# LED_Driver.net
KiCad netlist of a schematic drawn in Altium Designer
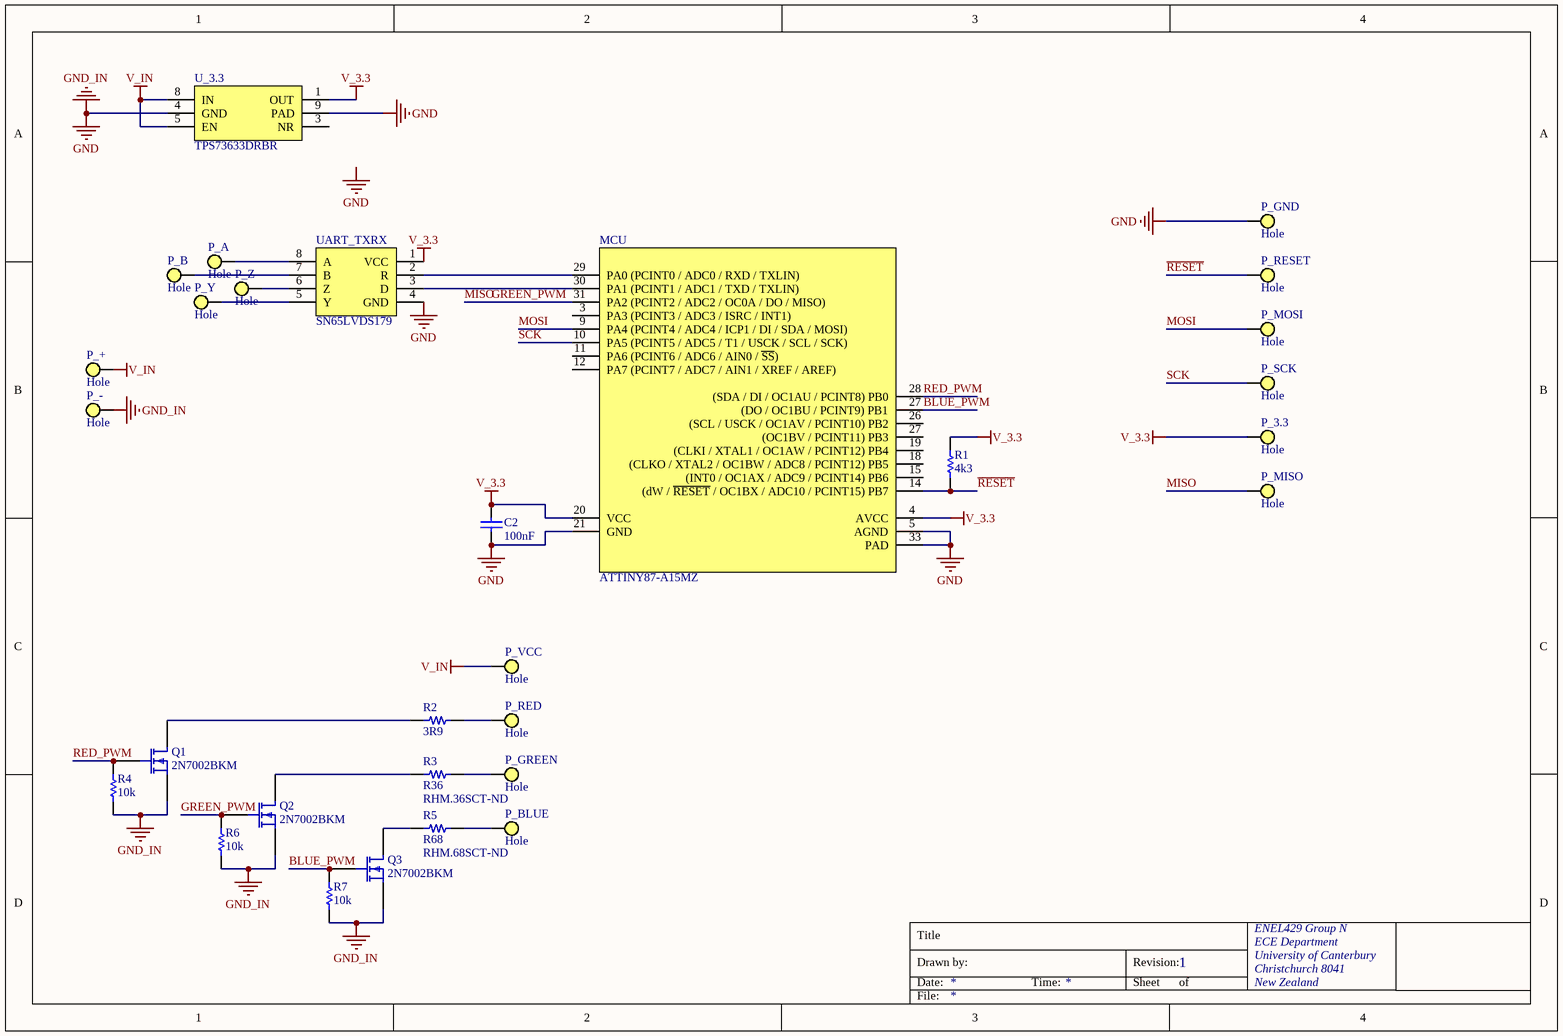
[diagram p0: LED_Driver.SchDoc]

(export (version "E")
  (design (tool "Eeschema 10.0.6"))
  (components
    (comp (ref "C2")
      (value "100nF")
      (footprint "0603")
      (description "CAP CER .10UF 50V X5R 0603")
      (fields (field (name "MANUFACTURER") "Taiyo Yuden") (field (name "PART NUMBER") "CP_100nF 0603"))
      (libsource (lib "ENEL429_4") (part "CP_100nF 0603"))
    )
    (comp (ref "MCU")
      (value "ATTINY87-A15MZ")
      (footprint "QFN50P500X500X100-32N")
      (description "MCU AVR 8K FLASH 15MHZ 32QFN")
      (fields (field (name "MANUFACTURER") "Atmel"))
      (libsource (lib "My Schematic Library") (part "ATTINY87-A15MZ"))
    )
    (comp (ref "P_+")
      (value "Hole")
      (footprint "Hole")
      (description "A hole to solder a wire to.")
      (libsource (lib "My Schematic Library") (part "Solder_Hole"))
    )
    (comp (ref "P_-")
      (value "Hole")
      (footprint "Hole")
      (description "A hole to solder a wire to.")
      (libsource (lib "My Schematic Library") (part "Solder_Hole"))
    )
    (comp (ref "P_3.3")
      (value "Hole")
      (footprint "Hole")
      (description "A hole to solder a wire to.")
      (libsource (lib "My Schematic Library") (part "Solder_Hole"))
    )
    (comp (ref "P_A")
      (value "Hole")
      (footprint "Hole")
      (description "A hole to solder a wire to.")
      (libsource (lib "My Schematic Library") (part "Solder_Hole"))
    )
    (comp (ref "P_B")
      (value "Hole")
      (footprint "Hole")
      (description "A hole to solder a wire to.")
      (libsource (lib "My Schematic Library") (part "Solder_Hole"))
    )
    (comp (ref "P_BLUE")
      (value "Hole")
      (footprint "Hole")
      (description "A hole to solder a wire to.")
      (libsource (lib "My Schematic Library") (part "Solder_Hole"))
    )
    (comp (ref "P_GND")
      (value "Hole")
      (footprint "Hole")
      (description "A hole to solder a wire to.")
      (libsource (lib "My Schematic Library") (part "Solder_Hole"))
    )
    (comp (ref "P_GREEN")
      (value "Hole")
      (footprint "Hole")
      (description "A hole to solder a wire to.")
      (libsource (lib "My Schematic Library") (part "Solder_Hole"))
    )
    (comp (ref "P_MISO")
      (value "Hole")
      (footprint "Hole")
      (description "A hole to solder a wire to.")
      (libsource (lib "My Schematic Library") (part "Solder_Hole"))
    )
    (comp (ref "P_MOSI")
      (value "Hole")
      (footprint "Hole")
      (description "A hole to solder a wire to.")
      (libsource (lib "My Schematic Library") (part "Solder_Hole"))
    )
    (comp (ref "P_RED")
      (value "Hole")
      (footprint "Hole")
      (description "A hole to solder a wire to.")
      (libsource (lib "My Schematic Library") (part "Solder_Hole"))
    )
    (comp (ref "P_RESET")
      (value "Hole")
      (footprint "Hole")
      (description "A hole to solder a wire to.")
      (libsource (lib "My Schematic Library") (part "Solder_Hole"))
    )
    (comp (ref "P_SCK")
      (value "Hole")
      (footprint "Hole")
      (description "A hole to solder a wire to.")
      (libsource (lib "My Schematic Library") (part "Solder_Hole"))
    )
    (comp (ref "P_VCC")
      (value "Hole")
      (footprint "Hole")
      (description "A hole to solder a wire to.")
      (libsource (lib "My Schematic Library") (part "Solder_Hole"))
    )
    (comp (ref "P_Y")
      (value "Hole")
      (footprint "Hole")
      (description "A hole to solder a wire to.")
      (libsource (lib "My Schematic Library") (part "Solder_Hole"))
    )
    (comp (ref "P_Z")
      (value "Hole")
      (footprint "Hole")
      (description "A hole to solder a wire to.")
      (libsource (lib "My Schematic Library") (part "Solder_Hole"))
    )
    (comp (ref "Q1")
      (value "2N7002BKM")
      (footprint "SOT883 / SC-101")
      (description "MOSFET N-CH 60V 450MA SOT883")
      (fields
        (field (name "MANUFACTURER") "NXP Semiconductors")
        (field (name "MANUFACTURER PART NUMBER") "2N7002BKM,315")
      )
      (libsource (lib "My Schematic Library") (part "2N7002BKM,315"))
    )
    (comp (ref "Q2")
      (value "2N7002BKM")
      (footprint "SOT883 / SC-101")
      (description "MOSFET N-CH 60V 450MA SOT883")
      (fields
        (field (name "MANUFACTURER") "NXP Semiconductors")
        (field (name "MANUFACTURER PART NUMBER") "2N7002BKM,315")
      )
      (libsource (lib "My Schematic Library") (part "2N7002BKM,315"))
    )
    (comp (ref "Q3")
      (value "2N7002BKM")
      (footprint "SOT883 / SC-101")
      (description "MOSFET N-CH 60V 450MA SOT883")
      (fields
        (field (name "MANUFACTURER") "NXP Semiconductors")
        (field (name "MANUFACTURER PART NUMBER") "2N7002BKM,315")
      )
      (libsource (lib "My Schematic Library") (part "2N7002BKM,315"))
    )
    (comp (ref "R1")
      (value "4k3")
      (footprint "0603")
      (description "RES 4.3K OHM 1/10W 5% 0603 SMD")
      (fields (field (name "MANUFACTURER") "Yageo") (field (name "PART NUMBER") "RS_4k3 0603"))
      (libsource (lib "ENEL429_4") (part "RS_4k3 0603"))
    )
    (comp (ref "R2")
      (value "3R9")
      (footprint "1210")
      (description "RES 3.9 OHM 1/2W 5% 1210 SMD")
      (fields
        (field (name "MANUFACTURER") "Vishay/Dale")
        (field (name "MANUFACTURER PART NUMBER") "CRCW12103R90JNEA")
      )
      (libsource (lib "My Schematic Library") (part "CRCW12103R90JNEA"))
    )
    (comp (ref "R3")
      (value "R36")
      (footprint "1210")
      (description "RES .36 OHM 1/2W 1% 1210 SMD")
      (fields
        (field (name "MANUFACTURER") "Rohm Semiconductor")
        (field (name "MANUFACTURER PART NUMBER") "MCR25JZHFLR360")
        (field (name "SUPPLIER PART NUMBER 1") "RHM.36SCT-ND")
      )
      (libsource (lib "My Schematic Library") (part "MCR25JZHFLR360"))
    )
    (comp (ref "R4")
      (value "10k")
      (footprint "0603")
      (description "RES 10.0K OHM 1/10W 1% 0603 SMD")
      (fields (field (name "MANUFACTURER") "Yageo") (field (name "PART NUMBER") "RS_10k 0603"))
      (libsource (lib "ENEL429_4") (part "RS_10k 0603"))
    )
    (comp (ref "R5")
      (value "R68")
      (footprint "1210")
      (description "RES .68 OHM 1/2W 1% 1210 SMD")
      (fields
        (field (name "MANUFACTURER") "Rohm Semiconductor")
        (field (name "MANUFACTURER PART NUMBER") "MCR25JZHFLR680")
        (field (name "SUPPLIER PART NUMBER 1") "RHM.68SCT-ND")
      )
      (libsource (lib "My Schematic Library") (part "MCR25JZHFLR680"))
    )
    (comp (ref "R6")
      (value "10k")
      (footprint "0603")
      (description "RES 10.0K OHM 1/10W 1% 0603 SMD")
      (fields (field (name "MANUFACTURER") "Yageo") (field (name "PART NUMBER") "RS_10k 0603"))
      (libsource (lib "ENEL429_4") (part "RS_10k 0603"))
    )
    (comp (ref "R7")
      (value "10k")
      (footprint "0603")
      (description "RES 10.0K OHM 1/10W 1% 0603 SMD")
      (fields (field (name "MANUFACTURER") "Yageo") (field (name "PART NUMBER") "RS_10k 0603"))
      (libsource (lib "ENEL429_4") (part "RS_10k 0603"))
    )
    (comp (ref "UART_TXRX")
      (value "SN65LVDS179")
      (footprint "TI - DGK / TSOP65P490X110-8L")
      (description "High-Speed Differential Line Driver and Receiver")
      (fields
        (field (name "MANUFACTURER") "Texas Instruments")
        (field (name "MANUFACTURER PART NUMBER") "SN65LVDS179DGK")
      )
      (libsource (lib "My Schematic Library") (part "SN65LVDS179DGK"))
    )
    (comp (ref "U_3.3")
      (value "TPS73633DRBR")
      (footprint "TI - DRB / QFN65P300X300X100-8L")
      (description "IC LDO REG 400MA NO CAP 8-SON")
      (fields (field (name "MANUFACTURER") "Texas Instruments"))
      (libsource (lib "My Schematic Library") (part "TPS73633DRBR"))
    )
  )
  (nets
    (net (code "1") (name "/BLUE_PWM") (class "Default")
      (node (ref "MCU") (pin "27") (pinfunction "(DO_/_OC1BU_/_PCINT9)_PB1_27") (pintype "passive"))
      (node (ref "Q3") (pin "1") (pinfunction "G_1") (pintype "passive"))
      (node (ref "R7") (pin "2") (pinfunction "2_2") (pintype "passive"))
    )
    (net (code "2") (name "/GREEN_PWM") (class "Default")
      (node (ref "MCU") (pin "31") (pinfunction "PA2_(PCINT2_/_ADC2_/_OC0A_/_DO_/_MISO)_31") (pintype "passive"))
      (node (ref "P_MISO") (pin "1") (pintype "passive"))
      (node (ref "Q2") (pin "1") (pinfunction "G_1") (pintype "passive"))
      (node (ref "R6") (pin "2") (pinfunction "2_2") (pintype "passive"))
    )
    (net (code "3") (name "/MOSI") (class "Default")
      (node (ref "MCU") (pin "9") (pinfunction "PA4_(PCINT4_/_ADC4_/_ICP1_/_DI_/_SDA_/_MOSI)_9") (pintype "passive"))
      (node (ref "P_MOSI") (pin "1") (pintype "passive"))
    )
    (net (code "4") (name "/RED_PWM") (class "Default")
      (node (ref "MCU") (pin "28") (pinfunction "(SDA_/_DI_/_OC1AU_/_PCINT8)_PB0_28") (pintype "passive"))
      (node (ref "Q1") (pin "1") (pinfunction "G_1") (pintype "passive"))
      (node (ref "R4") (pin "2") (pinfunction "2_2") (pintype "passive"))
    )
    (net (code "5") (name "/SCK") (class "Default")
      (node (ref "MCU") (pin "10") (pinfunction "PA5_(PCINT5_/_ADC5_/_T1_/_USCK_/_SCL_/_SCK)_10") (pintype "passive"))
      (node (ref "P_SCK") (pin "1") (pintype "passive"))
    )
    (net (code "6") (name "/~{RESET}") (class "Default")
      (node (ref "MCU") (pin "14") (pinfunction "(dW_/_~{RESET}_/_OC1BX_/_ADC10_/_PCINT15)_PB7_14") (pintype "passive"))
      (node (ref "P_RESET") (pin "1") (pintype "passive"))
      (node (ref "R1") (pin "1") (pinfunction "1_1") (pintype "passive"))
    )
    (net (code "7") (name "GND") (class "Default")
      (node (ref "C2") (pin "1") (pinfunction "1_1") (pintype "passive"))
      (node (ref "MCU") (pin "21") (pinfunction "GND_21") (pintype "passive"))
      (node (ref "MCU") (pin "33") (pinfunction "PAD_33") (pintype "passive"))
      (node (ref "MCU") (pin "5") (pinfunction "AGND_5") (pintype "passive"))
      (node (ref "P_-") (pin "1") (pintype "passive"))
      (node (ref "P_GND") (pin "1") (pintype "passive"))
      (node (ref "Q1") (pin "2") (pinfunction "S_2") (pintype "passive"))
      (node (ref "Q2") (pin "2") (pinfunction "S_2") (pintype "passive"))
      (node (ref "Q3") (pin "2") (pinfunction "S_2") (pintype "passive"))
      (node (ref "R4") (pin "1") (pinfunction "1_1") (pintype "passive"))
      (node (ref "R6") (pin "1") (pinfunction "1_1") (pintype "passive"))
      (node (ref "R7") (pin "1") (pinfunction "1_1") (pintype "passive"))
      (node (ref "UART_TXRX") (pin "4") (pinfunction "GND_4") (pintype "passive"))
      (node (ref "U_3.3") (pin "4") (pinfunction "GND_4") (pintype "passive"))
      (node (ref "U_3.3") (pin "9") (pinfunction "PAD_9") (pintype "passive"))
    )
    (net (code "8") (name "Net-(MCU-PA0_(PCINT0_{slash}_ADC0_{slash}_RXD_{slash}_TXLIN))") (class "Default")
      (node (ref "MCU") (pin "29") (pinfunction "PA0_(PCINT0_/_ADC0_/_RXD_/_TXLIN)_29") (pintype "passive"))
      (node (ref "UART_TXRX") (pin "2") (pinfunction "R_2") (pintype "passive"))
    )
    (net (code "9") (name "Net-(MCU-PA1_(PCINT1_{slash}_ADC1_{slash}_TXD_{slash}_TXLIN))") (class "Default")
      (node (ref "MCU") (pin "30") (pinfunction "PA1_(PCINT1_/_ADC1_/_TXD_/_TXLIN)_30") (pintype "passive"))
      (node (ref "UART_TXRX") (pin "3") (pinfunction "D_3") (pintype "passive"))
    )
    (net (code "10") (name "Net-(P_BLUE-Pad1)") (class "Default")
      (node (ref "P_BLUE") (pin "1") (pintype "passive"))
      (node (ref "R5") (pin "2") (pintype "passive"))
    )
    (net (code "11") (name "Net-(P_GREEN-Pad1)") (class "Default")
      (node (ref "P_GREEN") (pin "1") (pintype "passive"))
      (node (ref "R3") (pin "2") (pintype "passive"))
    )
    (net (code "12") (name "Net-(P_RED-Pad1)") (class "Default")
      (node (ref "P_RED") (pin "1") (pintype "passive"))
      (node (ref "R2") (pin "2") (pintype "passive"))
    )
    (net (code "13") (name "Net-(Q1-D)") (class "Default")
      (node (ref "Q1") (pin "3") (pinfunction "D_3") (pintype "passive"))
      (node (ref "R2") (pin "1") (pintype "passive"))
    )
    (net (code "14") (name "Net-(Q2-D)") (class "Default")
      (node (ref "Q2") (pin "3") (pinfunction "D_3") (pintype "passive"))
      (node (ref "R3") (pin "1") (pintype "passive"))
    )
    (net (code "15") (name "Net-(Q3-D)") (class "Default")
      (node (ref "Q3") (pin "3") (pinfunction "D_3") (pintype "passive"))
      (node (ref "R5") (pin "1") (pintype "passive"))
    )
    (net (code "16") (name "Net-(UART_TXRX-A)") (class "Default")
      (node (ref "P_A") (pin "1") (pintype "passive"))
      (node (ref "UART_TXRX") (pin "8") (pinfunction "A_8") (pintype "passive"))
    )
    (net (code "17") (name "Net-(UART_TXRX-B)") (class "Default")
      (node (ref "P_B") (pin "1") (pintype "passive"))
      (node (ref "UART_TXRX") (pin "7") (pinfunction "B_7") (pintype "passive"))
    )
    (net (code "18") (name "Net-(UART_TXRX-Y)") (class "Default")
      (node (ref "P_Y") (pin "1") (pintype "passive"))
      (node (ref "UART_TXRX") (pin "5") (pinfunction "Y_5") (pintype "passive"))
    )
    (net (code "19") (name "Net-(UART_TXRX-Z)") (class "Default")
      (node (ref "P_Z") (pin "1") (pintype "passive"))
      (node (ref "UART_TXRX") (pin "6") (pinfunction "Z_6") (pintype "passive"))
    )
    (net (code "20") (name "V_3.3") (class "Default")
      (node (ref "C2") (pin "2") (pinfunction "2_2") (pintype "passive"))
      (node (ref "MCU") (pin "20") (pinfunction "VCC_20") (pintype "passive"))
      (node (ref "MCU") (pin "4") (pinfunction "AVCC_4") (pintype "passive"))
      (node (ref "P_3.3") (pin "1") (pintype "passive"))
      (node (ref "R1") (pin "2") (pinfunction "2_2") (pintype "passive"))
      (node (ref "UART_TXRX") (pin "1") (pinfunction "VCC_1") (pintype "passive"))
      (node (ref "U_3.3") (pin "1") (pinfunction "OUT_1") (pintype "passive"))
    )
    (net (code "21") (name "V_IN") (class "Default")
      (node (ref "P_+") (pin "1") (pintype "passive"))
      (node (ref "P_VCC") (pin "1") (pintype "passive"))
      (node (ref "U_3.3") (pin "5") (pinfunction "EN_5") (pintype "passive"))
      (node (ref "U_3.3") (pin "8") (pinfunction "IN_8") (pintype "passive"))
    )
    (net (code "22") (name "unconnected-(MCU-(CLKI_{slash}_XTAL1_{slash}_OC1AW_{slash}_PCINT12)_PB4-Pad19)") (class "Default")
      (node (ref "MCU") (pin "19") (pinfunction "(CLKI_/_XTAL1_/_OC1AW_/_PCINT12)_PB4_19") (pintype "passive"))
    )
    (net (code "23") (name "unconnected-(MCU-(CLKO_{slash}_XTAL2_{slash}_OC1BW_{slash}_ADC8_{slash}_PCINT12)_PB5-Pad18)") (class "Default")
      (node (ref "MCU") (pin "18") (pinfunction "(CLKO_/_XTAL2_/_OC1BW_/_ADC8_/_PCINT12)_PB5_18") (pintype "passive"))
    )
    (net (code "24") (name "unconnected-(MCU-(INT0_{slash}_OC1AX_{slash}_ADC9_{slash}_PCINT14)_PB6-Pad15)") (class "Default")
      (node (ref "MCU") (pin "15") (pinfunction "(INT0_/_OC1AX_/_ADC9_/_PCINT14)_PB6_15") (pintype "passive"))
    )
    (net (code "25") (name "unconnected-(MCU-(OC1BV_{slash}_PCINT11)_PB3-Pad27)") (class "Default")
      (node (ref "MCU") (pin "27") (pinfunction "(OC1BV_/_PCINT11)_PB3_27") (pintype "passive"))
    )
    (net (code "26") (name "unconnected-(MCU-(SCL_{slash}_USCK_{slash}_OC1AV_{slash}_PCINT10)_PB2-Pad26)") (class "Default")
      (node (ref "MCU") (pin "26") (pinfunction "(SCL_/_USCK_/_OC1AV_/_PCINT10)_PB2_26") (pintype "passive"))
    )
    (net (code "27") (name "unconnected-(MCU-PA3_(PCINT3_{slash}_ADC3_{slash}_ISRC_{slash}_INT1)-Pad3)") (class "Default")
      (node (ref "MCU") (pin "3") (pinfunction "PA3_(PCINT3_/_ADC3_/_ISRC_/_INT1)_3") (pintype "passive"))
    )
    (net (code "28") (name "unconnected-(MCU-PA6_(PCINT6_{slash}_ADC6_{slash}_AIN0_{slash}_~{SS})-Pad11)") (class "Default")
      (node (ref "MCU") (pin "11") (pinfunction "PA6_(PCINT6_/_ADC6_/_AIN0_/_~{SS})_11") (pintype "passive"))
    )
    (net (code "29") (name "unconnected-(MCU-PA7_(PCINT7_{slash}_ADC7_{slash}_AIN1_{slash}_XREF_{slash}_AREF)-Pad12)") (class "Default")
      (node (ref "MCU") (pin "12") (pinfunction "PA7_(PCINT7_/_ADC7_/_AIN1_/_XREF_/_AREF)_12") (pintype "passive"))
    )
    (net (code "30") (name "unconnected-(U_3.3-NR-Pad3)") (class "Default")
      (node (ref "U_3.3") (pin "3") (pinfunction "NR_3") (pintype "passive"))
    )
  )
)
